# B105D.net
KiCad netlist of a schematic drawn in EAGLE
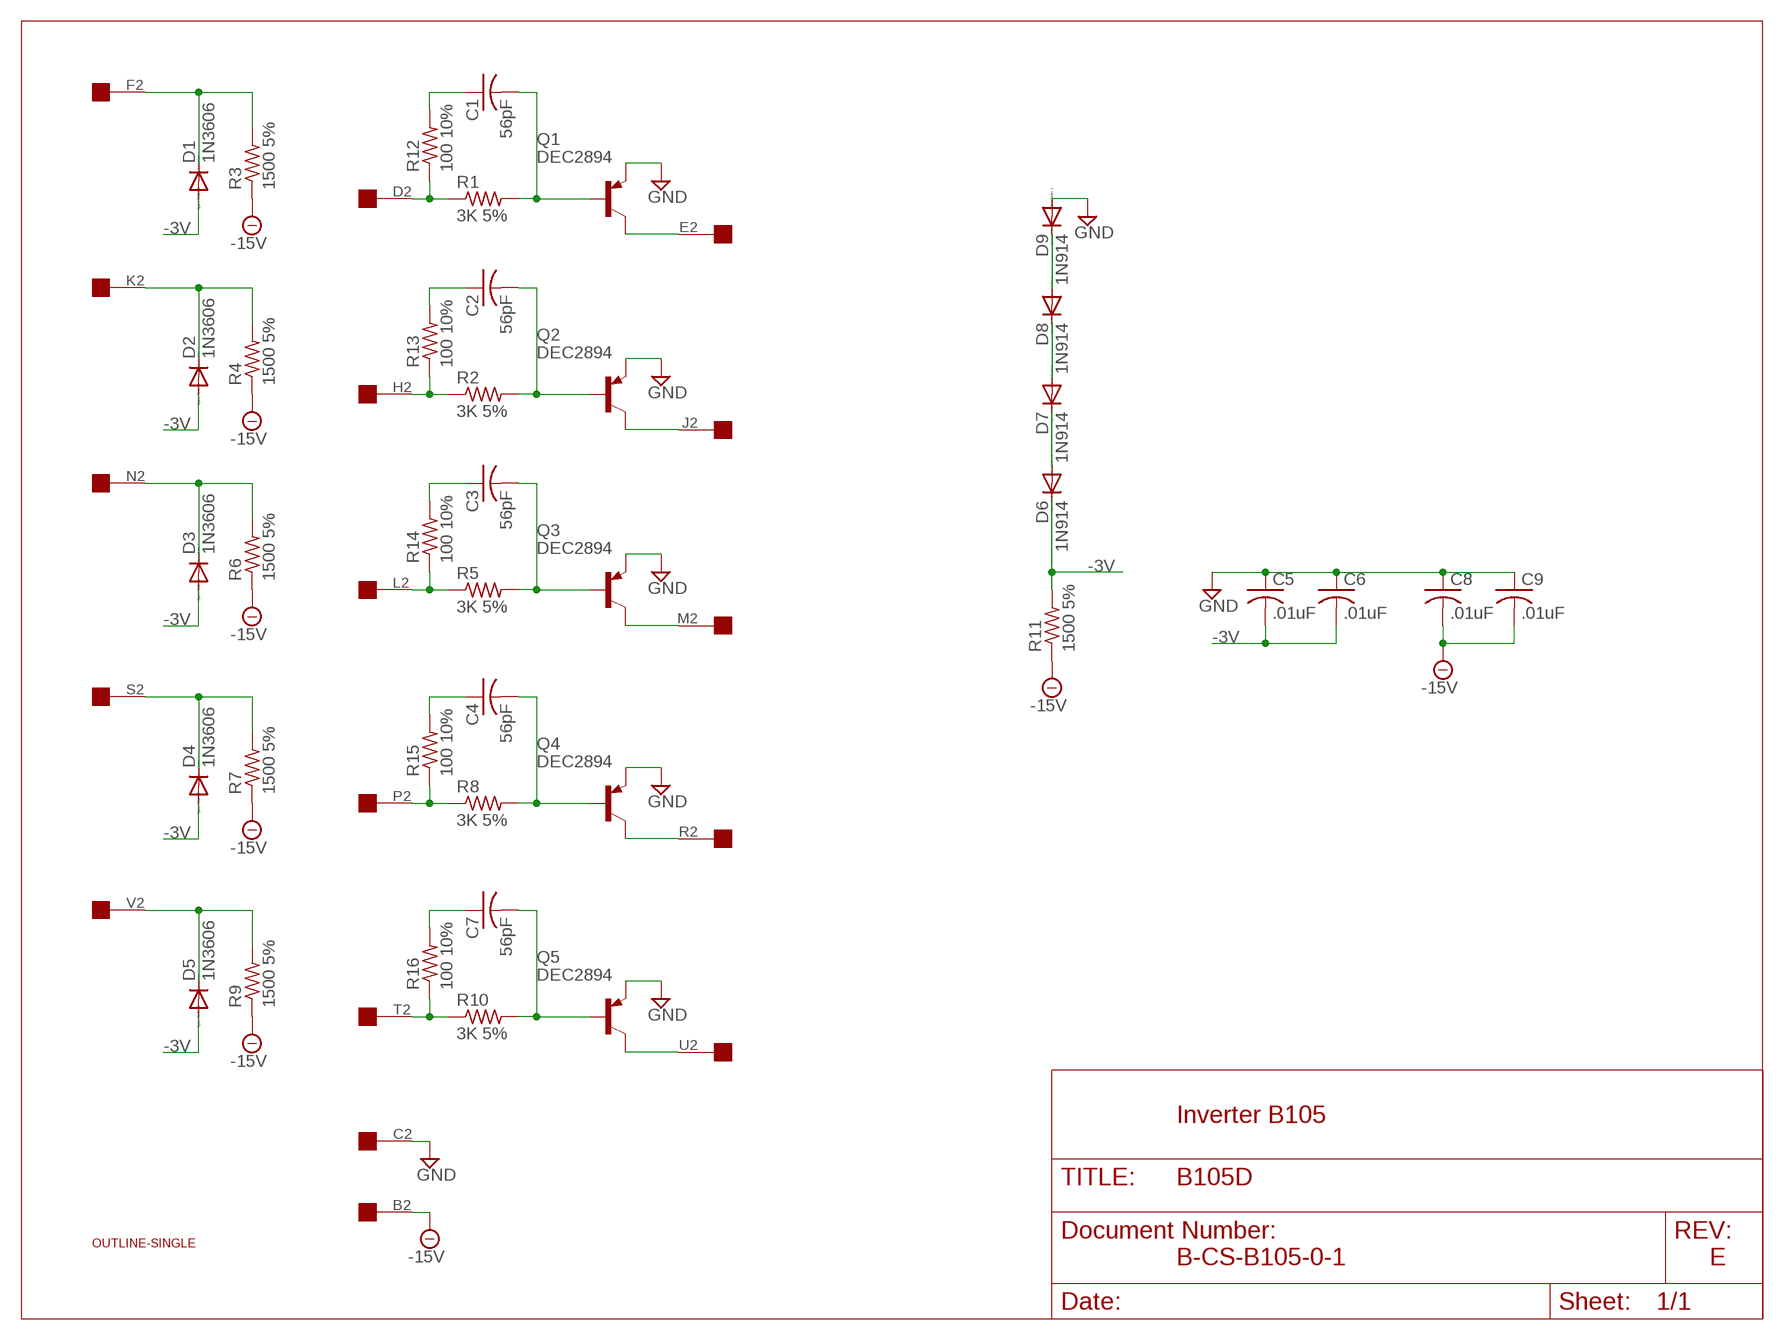
[diagram p0: schematic, sheet 1]

(export (version "E")
  (design (tool "Eeschema 10.0.6"))
  (components
    (comp (ref "C1")
      (value "56pF")
      (footprint "eagle-import:C102-043X133")
      (libsource (lib "eagle-import") (part "C-US102-043X133"))
    )
    (comp (ref "C2")
      (value "56pF")
      (footprint "eagle-import:C102-043X133")
      (libsource (lib "eagle-import") (part "C-US102-043X133"))
    )
    (comp (ref "C3")
      (value "56pF")
      (footprint "eagle-import:C102-043X133")
      (libsource (lib "eagle-import") (part "C-US102-043X133"))
    )
    (comp (ref "C4")
      (value "56pF")
      (footprint "eagle-import:C102-043X133")
      (libsource (lib "eagle-import") (part "C-US102-043X133"))
    )
    (comp (ref "C5")
      (value ".01uF")
      (footprint "eagle-import:C102-043X133")
      (libsource (lib "eagle-import") (part "C-US102-043X133"))
    )
    (comp (ref "C6")
      (value ".01uF")
      (footprint "eagle-import:C102-043X133")
      (libsource (lib "eagle-import") (part "C-US102-043X133"))
    )
    (comp (ref "C7")
      (value "56pF")
      (footprint "eagle-import:C102-043X133")
      (libsource (lib "eagle-import") (part "C-US102-043X133"))
    )
    (comp (ref "C8")
      (value ".01uF")
      (footprint "eagle-import:C102-043X133")
      (libsource (lib "eagle-import") (part "C-US102-043X133"))
    )
    (comp (ref "C9")
      (value ".01uF")
      (footprint "eagle-import:C102-043X133")
      (libsource (lib "eagle-import") (part "C-US102-043X133"))
    )
    (comp (ref "D1")
      (value "1N3606")
      (footprint "eagle-import:DO35-10")
      (libsource (lib "eagle-import") (part "1N4148DO35-10"))
    )
    (comp (ref "D2")
      (value "1N3606")
      (footprint "eagle-import:DO35-10")
      (libsource (lib "eagle-import") (part "1N4148DO35-10"))
    )
    (comp (ref "D3")
      (value "1N3606")
      (footprint "eagle-import:DO35-10")
      (libsource (lib "eagle-import") (part "1N4148DO35-10"))
    )
    (comp (ref "D4")
      (value "1N3606")
      (footprint "eagle-import:DO35-10")
      (libsource (lib "eagle-import") (part "1N4148DO35-10"))
    )
    (comp (ref "D5")
      (value "1N3606")
      (footprint "eagle-import:DO35-10")
      (libsource (lib "eagle-import") (part "1N4148DO35-10"))
    )
    (comp (ref "D6")
      (value "1N914")
      (footprint "eagle-import:DO35-10")
      (libsource (lib "eagle-import") (part "1N4148DO35-10"))
    )
    (comp (ref "D7")
      (value "1N914")
      (footprint "eagle-import:DO35-10")
      (libsource (lib "eagle-import") (part "1N4148DO35-10"))
    )
    (comp (ref "D8")
      (value "1N914")
      (footprint "eagle-import:DO35-10")
      (libsource (lib "eagle-import") (part "1N4148DO35-10"))
    )
    (comp (ref "D9")
      (value "1N914")
      (footprint "eagle-import:DO35-10")
      (libsource (lib "eagle-import") (part "1N4148DO35-10"))
    )
    (comp (ref "Q1")
      (value "DEC2894")
      (footprint "eagle-import:TO39")
      (libsource (lib "eagle-import") (part "2N2904"))
    )
    (comp (ref "Q2")
      (value "DEC2894")
      (footprint "eagle-import:TO39")
      (libsource (lib "eagle-import") (part "2N2904"))
    )
    (comp (ref "Q3")
      (value "DEC2894")
      (footprint "eagle-import:TO39")
      (libsource (lib "eagle-import") (part "2N2904"))
    )
    (comp (ref "Q4")
      (value "DEC2894")
      (footprint "eagle-import:TO39")
      (libsource (lib "eagle-import") (part "2N2904"))
    )
    (comp (ref "Q5")
      (value "DEC2894")
      (footprint "eagle-import:TO39")
      (libsource (lib "eagle-import") (part "2N2904"))
    )
    (comp (ref "R1")
      (value "3K 5%")
      (footprint "eagle-import:0207_10")
      (libsource (lib "eagle-import") (part "R-US_0207/10"))
    )
    (comp (ref "R2")
      (value "3K 5%")
      (footprint "eagle-import:0207_10")
      (libsource (lib "eagle-import") (part "R-US_0207/10"))
    )
    (comp (ref "R3")
      (value "1500 5%")
      (footprint "eagle-import:0207_10")
      (libsource (lib "eagle-import") (part "R-US_0207/10"))
    )
    (comp (ref "R4")
      (value "1500 5%")
      (footprint "eagle-import:0207_10")
      (libsource (lib "eagle-import") (part "R-US_0207/10"))
    )
    (comp (ref "R5")
      (value "3K 5%")
      (footprint "eagle-import:0207_10")
      (libsource (lib "eagle-import") (part "R-US_0207/10"))
    )
    (comp (ref "R6")
      (value "1500 5%")
      (footprint "eagle-import:0207_10")
      (libsource (lib "eagle-import") (part "R-US_0207/10"))
    )
    (comp (ref "R7")
      (value "1500 5%")
      (footprint "eagle-import:0207_10")
      (libsource (lib "eagle-import") (part "R-US_0207/10"))
    )
    (comp (ref "R8")
      (value "3K 5%")
      (footprint "eagle-import:0207_10")
      (libsource (lib "eagle-import") (part "R-US_0207/10"))
    )
    (comp (ref "R9")
      (value "1500 5%")
      (footprint "eagle-import:0207_10")
      (libsource (lib "eagle-import") (part "R-US_0207/10"))
    )
    (comp (ref "R10")
      (value "3K 5%")
      (footprint "eagle-import:0207_10")
      (libsource (lib "eagle-import") (part "R-US_0207/10"))
    )
    (comp (ref "R11")
      (value "1500 5%")
      (footprint "eagle-import:0207_10")
      (libsource (lib "eagle-import") (part "R-US_0207/10"))
    )
    (comp (ref "R12")
      (value "100 10%")
      (footprint "eagle-import:0207_10")
      (libsource (lib "eagle-import") (part "R-US_0207/10"))
    )
    (comp (ref "R13")
      (value "100 10%")
      (footprint "eagle-import:0207_10")
      (libsource (lib "eagle-import") (part "R-US_0207/10"))
    )
    (comp (ref "R14")
      (value "100 10%")
      (footprint "eagle-import:0207_10")
      (libsource (lib "eagle-import") (part "R-US_0207/10"))
    )
    (comp (ref "R15")
      (value "100 10%")
      (footprint "eagle-import:0207_10")
      (libsource (lib "eagle-import") (part "R-US_0207/10"))
    )
    (comp (ref "R16")
      (value "100 10%")
      (footprint "eagle-import:0207_10")
      (libsource (lib "eagle-import") (part "R-US_0207/10"))
    )
    (comp (ref "U$1")
      (value "OUTLINE-SINGLE")
      (footprint "eagle-import:SINGLE")
      (libsource (lib "eagle-import") (part "OUTLINE-SINGLE"))
    )
    (comp (ref "U$2")
      (value "EDGE-1")
      (footprint "eagle-import:EDGE-CON1")
      (libsource (lib "eagle-import") (part "EDGE-1"))
    )
  )
  (nets
    (net (code "1") (name "-15V") (class "Default")
      (node (ref "C8") (pin "2") (pinfunction "2_2") (pintype "passive"))
      (node (ref "C9") (pin "2") (pinfunction "2_2") (pintype "passive"))
      (node (ref "R11") (pin "1") (pinfunction "1_1") (pintype "passive"))
      (node (ref "R3") (pin "1") (pinfunction "1_1") (pintype "passive"))
      (node (ref "R4") (pin "1") (pinfunction "1_1") (pintype "passive"))
      (node (ref "R6") (pin "1") (pinfunction "1_1") (pintype "passive"))
      (node (ref "R7") (pin "1") (pinfunction "1_1") (pintype "passive"))
      (node (ref "R9") (pin "1") (pinfunction "1_1") (pintype "passive"))
      (node (ref "U$2") (pin "B2") (pinfunction "1_B2") (pintype "bidirectional"))
    )
    (net (code "2") (name "/-3V") (class "Default")
      (node (ref "C5") (pin "2") (pinfunction "2_2") (pintype "passive"))
      (node (ref "C6") (pin "2") (pinfunction "2_2") (pintype "passive"))
      (node (ref "D1") (pin "A") (pinfunction "A_A") (pintype "passive"))
      (node (ref "D2") (pin "A") (pinfunction "A_A") (pintype "passive"))
      (node (ref "D3") (pin "A") (pinfunction "A_A") (pintype "passive"))
      (node (ref "D4") (pin "A") (pinfunction "A_A") (pintype "passive"))
      (node (ref "D5") (pin "A") (pinfunction "A_A") (pintype "passive"))
      (node (ref "D6") (pin "C") (pinfunction "C_C") (pintype "passive"))
      (node (ref "R11") (pin "2") (pinfunction "2_2") (pintype "passive"))
    )
    (net (code "3") (name "GND") (class "Default")
      (node (ref "C5") (pin "1") (pinfunction "1_1") (pintype "passive"))
      (node (ref "C6") (pin "1") (pinfunction "1_1") (pintype "passive"))
      (node (ref "C8") (pin "1") (pinfunction "1_1") (pintype "passive"))
      (node (ref "C9") (pin "1") (pinfunction "1_1") (pintype "passive"))
      (node (ref "D9") (pin "A") (pinfunction "A_A") (pintype "passive"))
      (node (ref "Q1") (pin "1") (pinfunction "E_1") (pintype "passive"))
      (node (ref "Q2") (pin "1") (pinfunction "E_1") (pintype "passive"))
      (node (ref "Q3") (pin "1") (pinfunction "E_1") (pintype "passive"))
      (node (ref "Q4") (pin "1") (pinfunction "E_1") (pintype "passive"))
      (node (ref "Q5") (pin "1") (pinfunction "E_1") (pintype "passive"))
      (node (ref "U$2") (pin "C2") (pinfunction "1_C2") (pintype "bidirectional"))
    )
    (net (code "4") (name "Net-(C1-Pad1)") (class "Default")
      (node (ref "C1") (pin "1") (pinfunction "1_1") (pintype "passive"))
      (node (ref "R12") (pin "2") (pinfunction "2_2") (pintype "passive"))
    )
    (net (code "5") (name "Net-(C2-Pad1)") (class "Default")
      (node (ref "C2") (pin "1") (pinfunction "1_1") (pintype "passive"))
      (node (ref "R13") (pin "2") (pinfunction "2_2") (pintype "passive"))
    )
    (net (code "6") (name "Net-(C3-Pad1)") (class "Default")
      (node (ref "C3") (pin "1") (pinfunction "1_1") (pintype "passive"))
      (node (ref "R14") (pin "2") (pinfunction "2_2") (pintype "passive"))
    )
    (net (code "7") (name "Net-(C4-Pad1)") (class "Default")
      (node (ref "C4") (pin "1") (pinfunction "1_1") (pintype "passive"))
      (node (ref "R15") (pin "2") (pinfunction "2_2") (pintype "passive"))
    )
    (net (code "8") (name "Net-(C7-Pad1)") (class "Default")
      (node (ref "C7") (pin "1") (pinfunction "1_1") (pintype "passive"))
      (node (ref "R16") (pin "2") (pinfunction "2_2") (pintype "passive"))
    )
    (net (code "9") (name "Net-(D6-PadA)") (class "Default")
      (node (ref "D6") (pin "A") (pinfunction "A_A") (pintype "passive"))
      (node (ref "D7") (pin "C") (pinfunction "C_C") (pintype "passive"))
    )
    (net (code "10") (name "Net-(D7-PadA)") (class "Default")
      (node (ref "D7") (pin "A") (pinfunction "A_A") (pintype "passive"))
      (node (ref "D8") (pin "C") (pinfunction "C_C") (pintype "passive"))
    )
    (net (code "11") (name "Net-(D8-PadA)") (class "Default")
      (node (ref "D8") (pin "A") (pinfunction "A_A") (pintype "passive"))
      (node (ref "D9") (pin "C") (pinfunction "C_C") (pintype "passive"))
    )
    (net (code "12") (name "Net-(Q1-B)") (class "Default")
      (node (ref "C1") (pin "2") (pinfunction "2_2") (pintype "passive"))
      (node (ref "Q1") (pin "2") (pinfunction "B_2") (pintype "passive"))
      (node (ref "R1") (pin "2") (pinfunction "2_2") (pintype "passive"))
    )
    (net (code "13") (name "Net-(Q1-C)") (class "Default")
      (node (ref "Q1") (pin "3") (pinfunction "C_3") (pintype "passive"))
      (node (ref "U$2") (pin "E2") (pinfunction "1_E2") (pintype "bidirectional"))
    )
    (net (code "14") (name "Net-(Q2-B)") (class "Default")
      (node (ref "C2") (pin "2") (pinfunction "2_2") (pintype "passive"))
      (node (ref "Q2") (pin "2") (pinfunction "B_2") (pintype "passive"))
      (node (ref "R2") (pin "2") (pinfunction "2_2") (pintype "passive"))
    )
    (net (code "15") (name "Net-(Q2-C)") (class "Default")
      (node (ref "Q2") (pin "3") (pinfunction "C_3") (pintype "passive"))
      (node (ref "U$2") (pin "J2") (pinfunction "1_J2") (pintype "bidirectional"))
    )
    (net (code "16") (name "Net-(Q3-B)") (class "Default")
      (node (ref "C3") (pin "2") (pinfunction "2_2") (pintype "passive"))
      (node (ref "Q3") (pin "2") (pinfunction "B_2") (pintype "passive"))
      (node (ref "R5") (pin "2") (pinfunction "2_2") (pintype "passive"))
    )
    (net (code "17") (name "Net-(Q3-C)") (class "Default")
      (node (ref "Q3") (pin "3") (pinfunction "C_3") (pintype "passive"))
      (node (ref "U$2") (pin "M2") (pinfunction "1_M2") (pintype "bidirectional"))
    )
    (net (code "18") (name "Net-(Q4-B)") (class "Default")
      (node (ref "C4") (pin "2") (pinfunction "2_2") (pintype "passive"))
      (node (ref "Q4") (pin "2") (pinfunction "B_2") (pintype "passive"))
      (node (ref "R8") (pin "2") (pinfunction "2_2") (pintype "passive"))
    )
    (net (code "19") (name "Net-(Q4-C)") (class "Default")
      (node (ref "Q4") (pin "3") (pinfunction "C_3") (pintype "passive"))
      (node (ref "U$2") (pin "R2") (pinfunction "1_R2") (pintype "bidirectional"))
    )
    (net (code "20") (name "Net-(Q5-B)") (class "Default")
      (node (ref "C7") (pin "2") (pinfunction "2_2") (pintype "passive"))
      (node (ref "Q5") (pin "2") (pinfunction "B_2") (pintype "passive"))
      (node (ref "R10") (pin "2") (pinfunction "2_2") (pintype "passive"))
    )
    (net (code "21") (name "Net-(Q5-C)") (class "Default")
      (node (ref "Q5") (pin "3") (pinfunction "C_3") (pintype "passive"))
      (node (ref "U$2") (pin "U2") (pinfunction "1_U2") (pintype "bidirectional"))
    )
    (net (code "22") (name "Net-(U$2D-1)") (class "Default")
      (node (ref "R1") (pin "1") (pinfunction "1_1") (pintype "passive"))
      (node (ref "R12") (pin "1") (pinfunction "1_1") (pintype "passive"))
      (node (ref "U$2") (pin "D2") (pinfunction "1_D2") (pintype "bidirectional"))
    )
    (net (code "23") (name "Net-(U$2F-1)") (class "Default")
      (node (ref "D1") (pin "C") (pinfunction "C_C") (pintype "passive"))
      (node (ref "R3") (pin "2") (pinfunction "2_2") (pintype "passive"))
      (node (ref "U$2") (pin "F2") (pinfunction "1_F2") (pintype "bidirectional"))
    )
    (net (code "24") (name "Net-(U$2G-1)") (class "Default")
      (node (ref "R13") (pin "1") (pinfunction "1_1") (pintype "passive"))
      (node (ref "R2") (pin "1") (pinfunction "1_1") (pintype "passive"))
      (node (ref "U$2") (pin "H2") (pinfunction "1_H2") (pintype "bidirectional"))
    )
    (net (code "25") (name "Net-(U$2I-1)") (class "Default")
      (node (ref "D2") (pin "C") (pinfunction "C_C") (pintype "passive"))
      (node (ref "R4") (pin "2") (pinfunction "2_2") (pintype "passive"))
      (node (ref "U$2") (pin "K2") (pinfunction "1_K2") (pintype "bidirectional"))
    )
    (net (code "26") (name "Net-(U$2J-1)") (class "Default")
      (node (ref "R14") (pin "1") (pinfunction "1_1") (pintype "passive"))
      (node (ref "R5") (pin "1") (pinfunction "1_1") (pintype "passive"))
      (node (ref "U$2") (pin "L2") (pinfunction "1_L2") (pintype "bidirectional"))
    )
    (net (code "27") (name "Net-(U$2L-1)") (class "Default")
      (node (ref "D3") (pin "C") (pinfunction "C_C") (pintype "passive"))
      (node (ref "R6") (pin "2") (pinfunction "2_2") (pintype "passive"))
      (node (ref "U$2") (pin "N2") (pinfunction "1_N2") (pintype "bidirectional"))
    )
    (net (code "28") (name "Net-(U$2M-1)") (class "Default")
      (node (ref "R15") (pin "1") (pinfunction "1_1") (pintype "passive"))
      (node (ref "R8") (pin "1") (pinfunction "1_1") (pintype "passive"))
      (node (ref "U$2") (pin "P2") (pinfunction "1_P2") (pintype "bidirectional"))
    )
    (net (code "29") (name "Net-(U$2O-1)") (class "Default")
      (node (ref "D4") (pin "C") (pinfunction "C_C") (pintype "passive"))
      (node (ref "R7") (pin "2") (pinfunction "2_2") (pintype "passive"))
      (node (ref "U$2") (pin "S2") (pinfunction "1_S2") (pintype "bidirectional"))
    )
    (net (code "30") (name "Net-(U$2P-1)") (class "Default")
      (node (ref "R10") (pin "1") (pinfunction "1_1") (pintype "passive"))
      (node (ref "R16") (pin "1") (pinfunction "1_1") (pintype "passive"))
      (node (ref "U$2") (pin "T2") (pinfunction "1_T2") (pintype "bidirectional"))
    )
    (net (code "31") (name "Net-(U$2R-1)") (class "Default")
      (node (ref "D5") (pin "C") (pinfunction "C_C") (pintype "passive"))
      (node (ref "R9") (pin "2") (pinfunction "2_2") (pintype "passive"))
      (node (ref "U$2") (pin "V2") (pinfunction "1_V2") (pintype "bidirectional"))
    )
  )
)
